# XBee-Explorer-DongleMiniV13.net
KiCad netlist of a schematic drawn in EAGLE
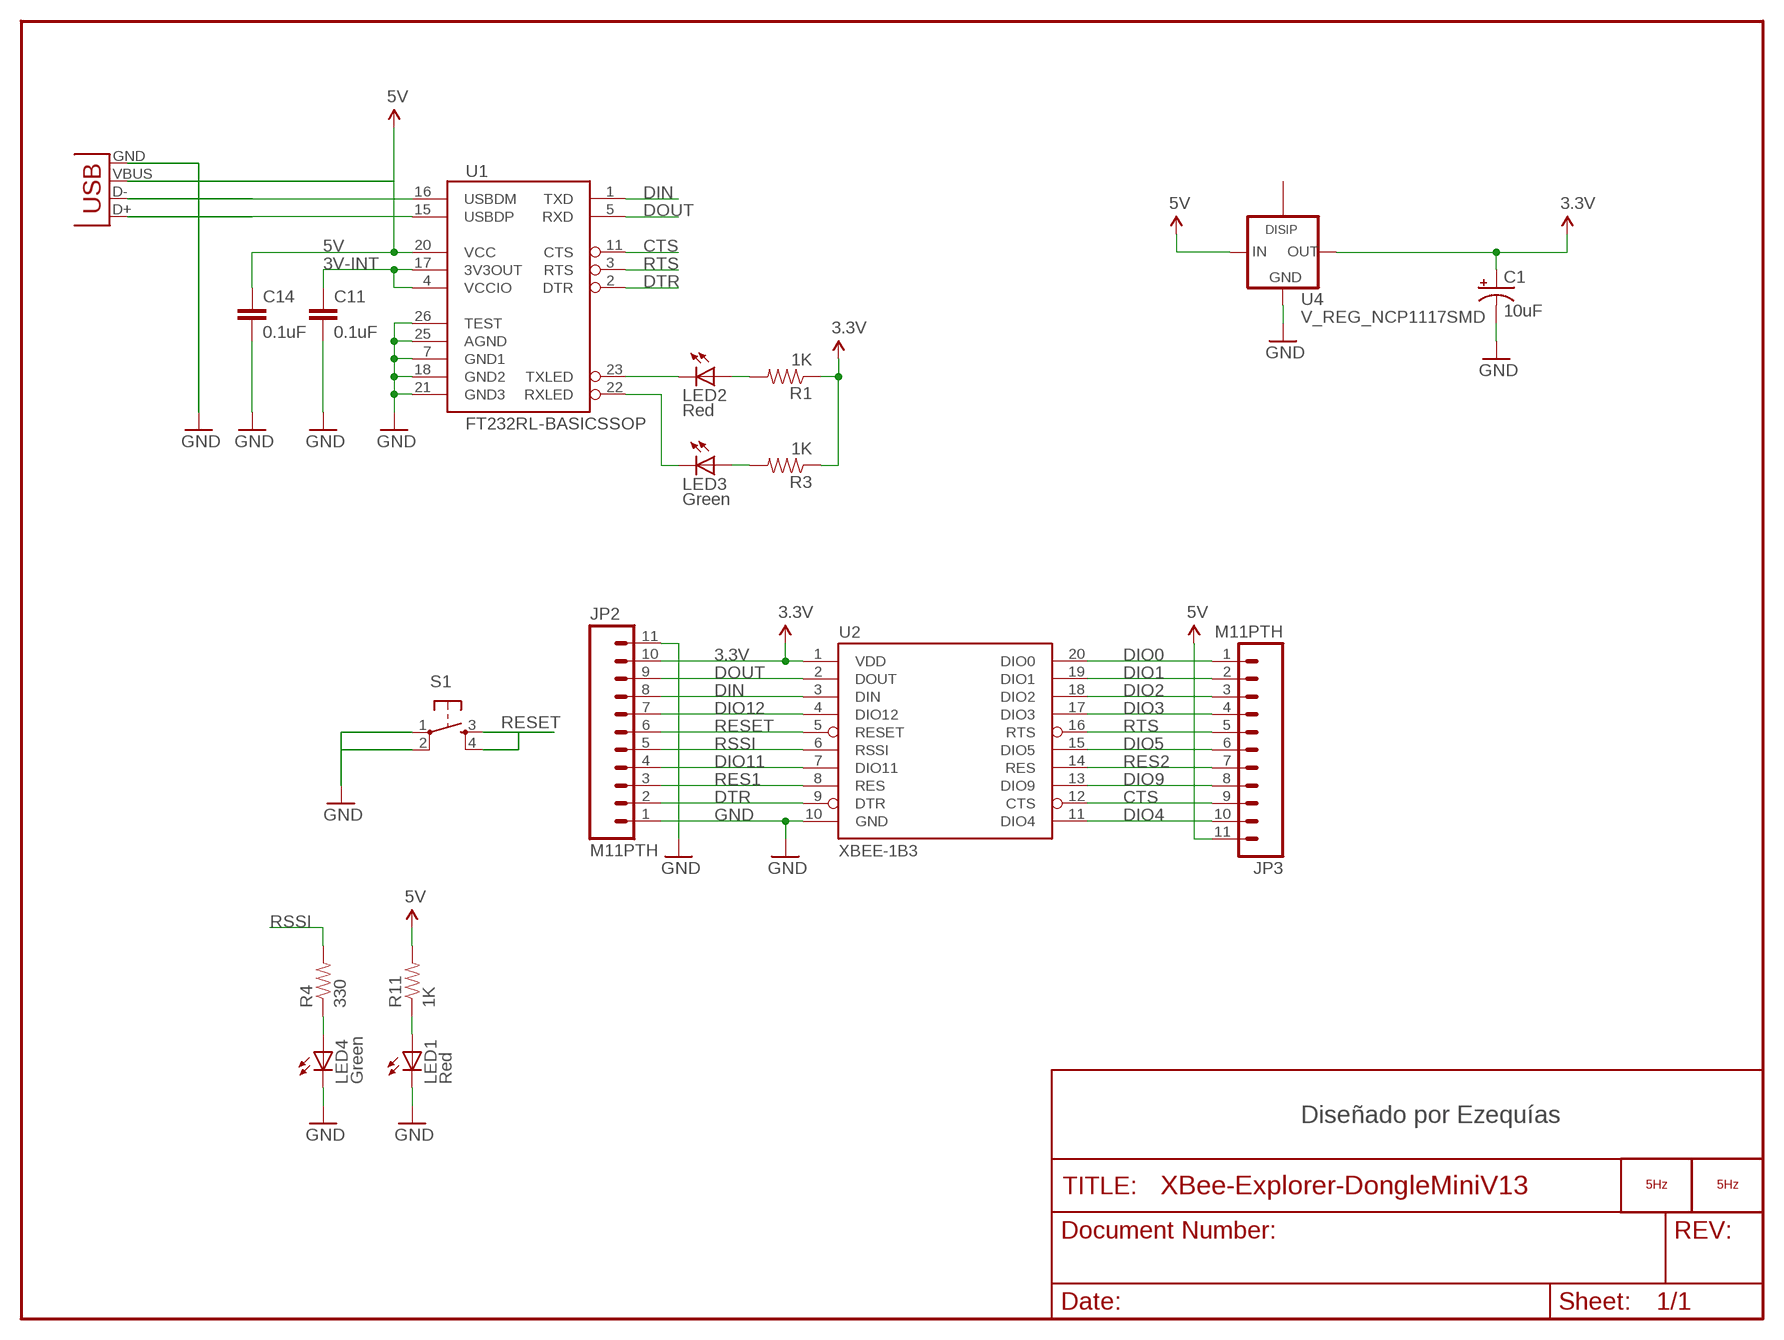
[diagram p0: schematic, sheet 1]

(export (version "E")
  (design (tool "Eeschema 10.0.6"))
  (components
    (comp (ref "C1")
      (value "10uF")
      (footprint "eagle-import:EIA3216")
      (libsource (lib "eagle-import") (part "CAP_POL1206"))
    )
    (comp (ref "C11")
      (value "0.1uF")
      (footprint "eagle-import:0402-CAP")
      (libsource (lib "eagle-import") (part "CAP0402-CAP"))
    )
    (comp (ref "C14")
      (value "0.1uF")
      (footprint "eagle-import:0402-CAP")
      (libsource (lib "eagle-import") (part "CAP0402-CAP"))
    )
    (comp (ref "JP2")
      (value "M11PTH")
      (footprint "eagle-import:1X11")
      (libsource (lib "eagle-import") (part "M11PTH"))
    )
    (comp (ref "JP3")
      (value "M11PTH")
      (footprint "eagle-import:1X11")
      (libsource (lib "eagle-import") (part "M11PTH"))
    )
    (comp (ref "LED1")
      (value "Red")
      (footprint "eagle-import:LED-0603")
      (libsource (lib "eagle-import") (part "LED0603"))
    )
    (comp (ref "LED2")
      (value "Red")
      (footprint "eagle-import:LED-0603")
      (libsource (lib "eagle-import") (part "LED0603"))
    )
    (comp (ref "LED3")
      (value "Green")
      (footprint "eagle-import:LED-0603")
      (libsource (lib "eagle-import") (part "LED0603"))
    )
    (comp (ref "LED4")
      (value "Green")
      (footprint "eagle-import:LED-0603")
      (libsource (lib "eagle-import") (part "LED0603"))
    )
    (comp (ref "LOGO1")
      (value "LOGO_5HZ_MAIN_10MM")
      (footprint "eagle-import:5HZ_LOGO_MAIN_10MM")
      (libsource (lib "eagle-import") (part "LOGO_5HZ_MAIN_10MM"))
    )
    (comp (ref "LOGO2")
      (value "LOGO_5HZ_H_10MM")
      (footprint "eagle-import:5HZ_LOGO_H_10MM")
      (libsource (lib "eagle-import") (part "LOGO_5HZ_H_10MM"))
    )
    (comp (ref "R1")
      (value "1K")
      (footprint "eagle-import:0603-RES")
      (libsource (lib "eagle-import") (part "RESISTOR0603-RES"))
    )
    (comp (ref "R3")
      (value "1K")
      (footprint "eagle-import:0603-RES")
      (libsource (lib "eagle-import") (part "RESISTOR0603-RES"))
    )
    (comp (ref "R4")
      (value "330")
      (footprint "eagle-import:0603-RES")
      (libsource (lib "eagle-import") (part "RESISTOR0603-RES"))
    )
    (comp (ref "R11")
      (value "1K")
      (footprint "eagle-import:0603-RES")
      (libsource (lib "eagle-import") (part "RESISTOR0603-RES"))
    )
    (comp (ref "S1")
      (value "TAC_SWITCHSMD")
      (footprint "eagle-import:TACTILE_SWITCH_SMD")
      (libsource (lib "eagle-import") (part "TAC_SWITCHSMD"))
    )
    (comp (ref "U1")
      (value "FT232RL-BASICSSOP")
      (footprint "eagle-import:SSOP28DB")
      (libsource (lib "eagle-import") (part "FT232RL-BASICSSOP"))
    )
    (comp (ref "U2")
      (value "XBEE-1B3")
      (footprint "eagle-import:XBEE-SMD")
      (libsource (lib "eagle-import") (part "XBEE-1B3"))
    )
    (comp (ref "U4")
      (value "V_REG_NCP1117SMD")
      (footprint "eagle-import:SOT223")
      (libsource (lib "eagle-import") (part "V_REG_NCP1117SMD"))
    )
    (comp (ref "X1")
      (value "USBSMD")
      (footprint "eagle-import:USB-MINIB")
      (libsource (lib "eagle-import") (part "USBSMD"))
    )
  )
  (nets
    (net (code "1") (name "/3V-INT") (class "Default")
      (node (ref "C11") (pin "1") (pinfunction "1_1") (pintype "passive"))
      (node (ref "U1") (pin "17") (pinfunction "3V3OUT_17") (pintype "output"))
      (node (ref "U1") (pin "4") (pinfunction "VCCIO_4") (pintype "power_in"))
    )
    (net (code "2") (name "/CTS") (class "Default")
      (node (ref "JP3") (pin "9") (pinfunction "9_9") (pintype "passive"))
      (node (ref "U1") (pin "11") (pinfunction "CTS_11") (pintype "bidirectional"))
      (node (ref "U2") (pin "12") (pinfunction "CTS_12") (pintype "output"))
    )
    (net (code "3") (name "/DIN") (class "Default")
      (node (ref "JP2") (pin "8") (pinfunction "8_8") (pintype "passive"))
      (node (ref "U1") (pin "1") (pinfunction "TXD_1") (pintype "output"))
      (node (ref "U2") (pin "3") (pinfunction "DIN_3") (pintype "input"))
    )
    (net (code "4") (name "/DIO0") (class "Default")
      (node (ref "JP3") (pin "1") (pinfunction "1_1") (pintype "passive"))
      (node (ref "U2") (pin "20") (pinfunction "DIO0_20") (pintype "bidirectional"))
    )
    (net (code "5") (name "/DIO1") (class "Default")
      (node (ref "JP3") (pin "2") (pinfunction "2_2") (pintype "passive"))
      (node (ref "U2") (pin "19") (pinfunction "DIO1_19") (pintype "bidirectional"))
    )
    (net (code "6") (name "/DIO2") (class "Default")
      (node (ref "JP3") (pin "3") (pinfunction "3_3") (pintype "passive"))
      (node (ref "U2") (pin "18") (pinfunction "DIO2_18") (pintype "bidirectional"))
    )
    (net (code "7") (name "/DIO3") (class "Default")
      (node (ref "JP3") (pin "4") (pinfunction "4_4") (pintype "passive"))
      (node (ref "U2") (pin "17") (pinfunction "DIO3_17") (pintype "bidirectional"))
    )
    (net (code "8") (name "/DIO4") (class "Default")
      (node (ref "JP3") (pin "10") (pinfunction "10_10") (pintype "passive"))
      (node (ref "U2") (pin "11") (pinfunction "DIO4_11") (pintype "bidirectional"))
    )
    (net (code "9") (name "/DIO5") (class "Default")
      (node (ref "JP3") (pin "6") (pinfunction "6_6") (pintype "passive"))
      (node (ref "U2") (pin "15") (pinfunction "DIO5_15") (pintype "bidirectional"))
    )
    (net (code "10") (name "/DIO9") (class "Default")
      (node (ref "JP3") (pin "8") (pinfunction "8_8") (pintype "passive"))
      (node (ref "U2") (pin "13") (pinfunction "DIO9_13") (pintype "bidirectional"))
    )
    (net (code "11") (name "/DIO11") (class "Default")
      (node (ref "JP2") (pin "4") (pinfunction "4_4") (pintype "passive"))
      (node (ref "U2") (pin "7") (pinfunction "DIO11_7") (pintype "bidirectional"))
    )
    (net (code "12") (name "/DIO12") (class "Default")
      (node (ref "JP2") (pin "7") (pinfunction "7_7") (pintype "passive"))
      (node (ref "U2") (pin "4") (pinfunction "DIO12_4") (pintype "bidirectional"))
    )
    (net (code "13") (name "/DOUT") (class "Default")
      (node (ref "JP2") (pin "9") (pinfunction "9_9") (pintype "passive"))
      (node (ref "U1") (pin "5") (pinfunction "RXD_5") (pintype "input"))
      (node (ref "U2") (pin "2") (pinfunction "DOUT_2") (pintype "output"))
    )
    (net (code "14") (name "/DTR") (class "Default")
      (node (ref "JP2") (pin "2") (pinfunction "2_2") (pintype "passive"))
      (node (ref "U1") (pin "2") (pinfunction "DTR_2") (pintype "bidirectional"))
      (node (ref "U2") (pin "9") (pinfunction "DTR_9") (pintype "bidirectional"))
    )
    (net (code "15") (name "/RES1") (class "Default")
      (node (ref "JP2") (pin "3") (pinfunction "3_3") (pintype "passive"))
      (node (ref "U2") (pin "8") (pinfunction "RES_8") (pintype "bidirectional"))
    )
    (net (code "16") (name "/RES2") (class "Default")
      (node (ref "JP3") (pin "7") (pinfunction "7_7") (pintype "passive"))
      (node (ref "U2") (pin "14") (pinfunction "RES_14") (pintype "bidirectional"))
    )
    (net (code "17") (name "/RESET") (class "Default")
      (node (ref "JP2") (pin "6") (pinfunction "6_6") (pintype "passive"))
      (node (ref "S1") (pin "3") (pinfunction "3_3") (pintype "passive"))
      (node (ref "S1") (pin "4") (pinfunction "4_4") (pintype "passive"))
      (node (ref "U2") (pin "5") (pinfunction "RESET_5") (pintype "input"))
    )
    (net (code "18") (name "/RSSI") (class "Default")
      (node (ref "JP2") (pin "5") (pinfunction "5_5") (pintype "passive"))
      (node (ref "R4") (pin "2") (pinfunction "2_2") (pintype "passive"))
      (node (ref "U2") (pin "6") (pinfunction "RSSI_6") (pintype "bidirectional"))
    )
    (net (code "19") (name "/RTS") (class "Default")
      (node (ref "JP3") (pin "5") (pinfunction "5_5") (pintype "passive"))
      (node (ref "U1") (pin "3") (pinfunction "RTS_3") (pintype "bidirectional"))
      (node (ref "U2") (pin "16") (pinfunction "RTS_16") (pintype "input"))
    )
    (net (code "20") (name "3.3V") (class "Default")
      (node (ref "C1") (pin "A") (pinfunction "+_A") (pintype "passive"))
      (node (ref "JP2") (pin "10") (pinfunction "10_10") (pintype "passive"))
      (node (ref "R1") (pin "1") (pinfunction "1_1") (pintype "passive"))
      (node (ref "R3") (pin "1") (pinfunction "1_1") (pintype "passive"))
      (node (ref "U2") (pin "1") (pinfunction "VDD_1") (pintype "power_in"))
      (node (ref "U4") (pin "2") (pinfunction "OUT_2") (pintype "output"))
    )
    (net (code "21") (name "5V") (class "Default")
      (node (ref "C14") (pin "1") (pinfunction "1_1") (pintype "passive"))
      (node (ref "JP3") (pin "11") (pinfunction "11_11") (pintype "passive"))
      (node (ref "R11") (pin "2") (pinfunction "2_2") (pintype "passive"))
      (node (ref "U1") (pin "20") (pinfunction "VCC_20") (pintype "power_in"))
      (node (ref "U4") (pin "3") (pinfunction "IN_3") (pintype "input"))
      (node (ref "X1") (pin "VBUS") (pinfunction "VBUS_VBUS") (pintype "bidirectional"))
    )
    (net (code "22") (name "GND") (class "Default")
      (node (ref "C1") (pin "C") (pinfunction "-_C") (pintype "passive"))
      (node (ref "C11") (pin "2") (pinfunction "2_2") (pintype "passive"))
      (node (ref "C14") (pin "2") (pinfunction "2_2") (pintype "passive"))
      (node (ref "JP2") (pin "1") (pinfunction "1_1") (pintype "passive"))
      (node (ref "JP2") (pin "11") (pinfunction "11_11") (pintype "passive"))
      (node (ref "LED1") (pin "C") (pinfunction "C_C") (pintype "passive"))
      (node (ref "LED4") (pin "C") (pinfunction "C_C") (pintype "passive"))
      (node (ref "S1") (pin "1") (pinfunction "1_1") (pintype "passive"))
      (node (ref "S1") (pin "2") (pinfunction "2_2") (pintype "passive"))
      (node (ref "U1") (pin "18") (pinfunction "GND2_18") (pintype "power_in"))
      (node (ref "U1") (pin "21") (pinfunction "GND3_21") (pintype "power_in"))
      (node (ref "U1") (pin "25") (pinfunction "AGND_25") (pintype "power_in"))
      (node (ref "U1") (pin "26") (pinfunction "TEST_26") (pintype "input"))
      (node (ref "U1") (pin "7") (pinfunction "GND1_7") (pintype "power_in"))
      (node (ref "U2") (pin "10") (pinfunction "GND_10") (pintype "power_in"))
      (node (ref "U4") (pin "1") (pinfunction "GND_1") (pintype "input"))
      (node (ref "X1") (pin "GND") (pinfunction "GND_GND") (pintype "bidirectional"))
    )
    (net (code "23") (name "Net-(LED1-PadA)") (class "Default")
      (node (ref "LED1") (pin "A") (pinfunction "A_A") (pintype "passive"))
      (node (ref "R11") (pin "1") (pinfunction "1_1") (pintype "passive"))
    )
    (net (code "24") (name "Net-(LED2-PadA)") (class "Default")
      (node (ref "LED2") (pin "A") (pinfunction "A_A") (pintype "passive"))
      (node (ref "R1") (pin "2") (pinfunction "2_2") (pintype "passive"))
    )
    (net (code "25") (name "Net-(LED3-PadA)") (class "Default")
      (node (ref "LED3") (pin "A") (pinfunction "A_A") (pintype "passive"))
      (node (ref "R3") (pin "2") (pinfunction "2_2") (pintype "passive"))
    )
    (net (code "26") (name "Net-(LED4-PadA)") (class "Default")
      (node (ref "LED4") (pin "A") (pinfunction "A_A") (pintype "passive"))
      (node (ref "R4") (pin "1") (pinfunction "1_1") (pintype "passive"))
    )
    (net (code "27") (name "Net-(U1-RXLED)") (class "Default")
      (node (ref "LED3") (pin "C") (pinfunction "C_C") (pintype "passive"))
      (node (ref "U1") (pin "22") (pinfunction "RXLED_22") (pintype "bidirectional"))
    )
    (net (code "28") (name "Net-(U1-TXLED)") (class "Default")
      (node (ref "LED2") (pin "C") (pinfunction "C_C") (pintype "passive"))
      (node (ref "U1") (pin "23") (pinfunction "TXLED_23") (pintype "bidirectional"))
    )
    (net (code "29") (name "Net-(U1-USBDM)") (class "Default")
      (node (ref "U1") (pin "16") (pinfunction "USBDM_16") (pintype "bidirectional"))
      (node (ref "X1") (pin "D-") (pinfunction "D-_D-") (pintype "bidirectional"))
    )
    (net (code "30") (name "Net-(U1-USBDP)") (class "Default")
      (node (ref "U1") (pin "15") (pinfunction "USBDP_15") (pintype "bidirectional"))
      (node (ref "X1") (pin "D+") (pinfunction "D+_D+") (pintype "bidirectional"))
    )
    (net (code "31") (name "unconnected-(U4-P$1-Pad4)") (class "Default")
      (node (ref "U4") (pin "4") (pinfunction "P$1_4") (pintype "bidirectional"))
    )
  )
)
